# ruwido-usb.net
KiCad netlist of a schematic drawn in EAGLE
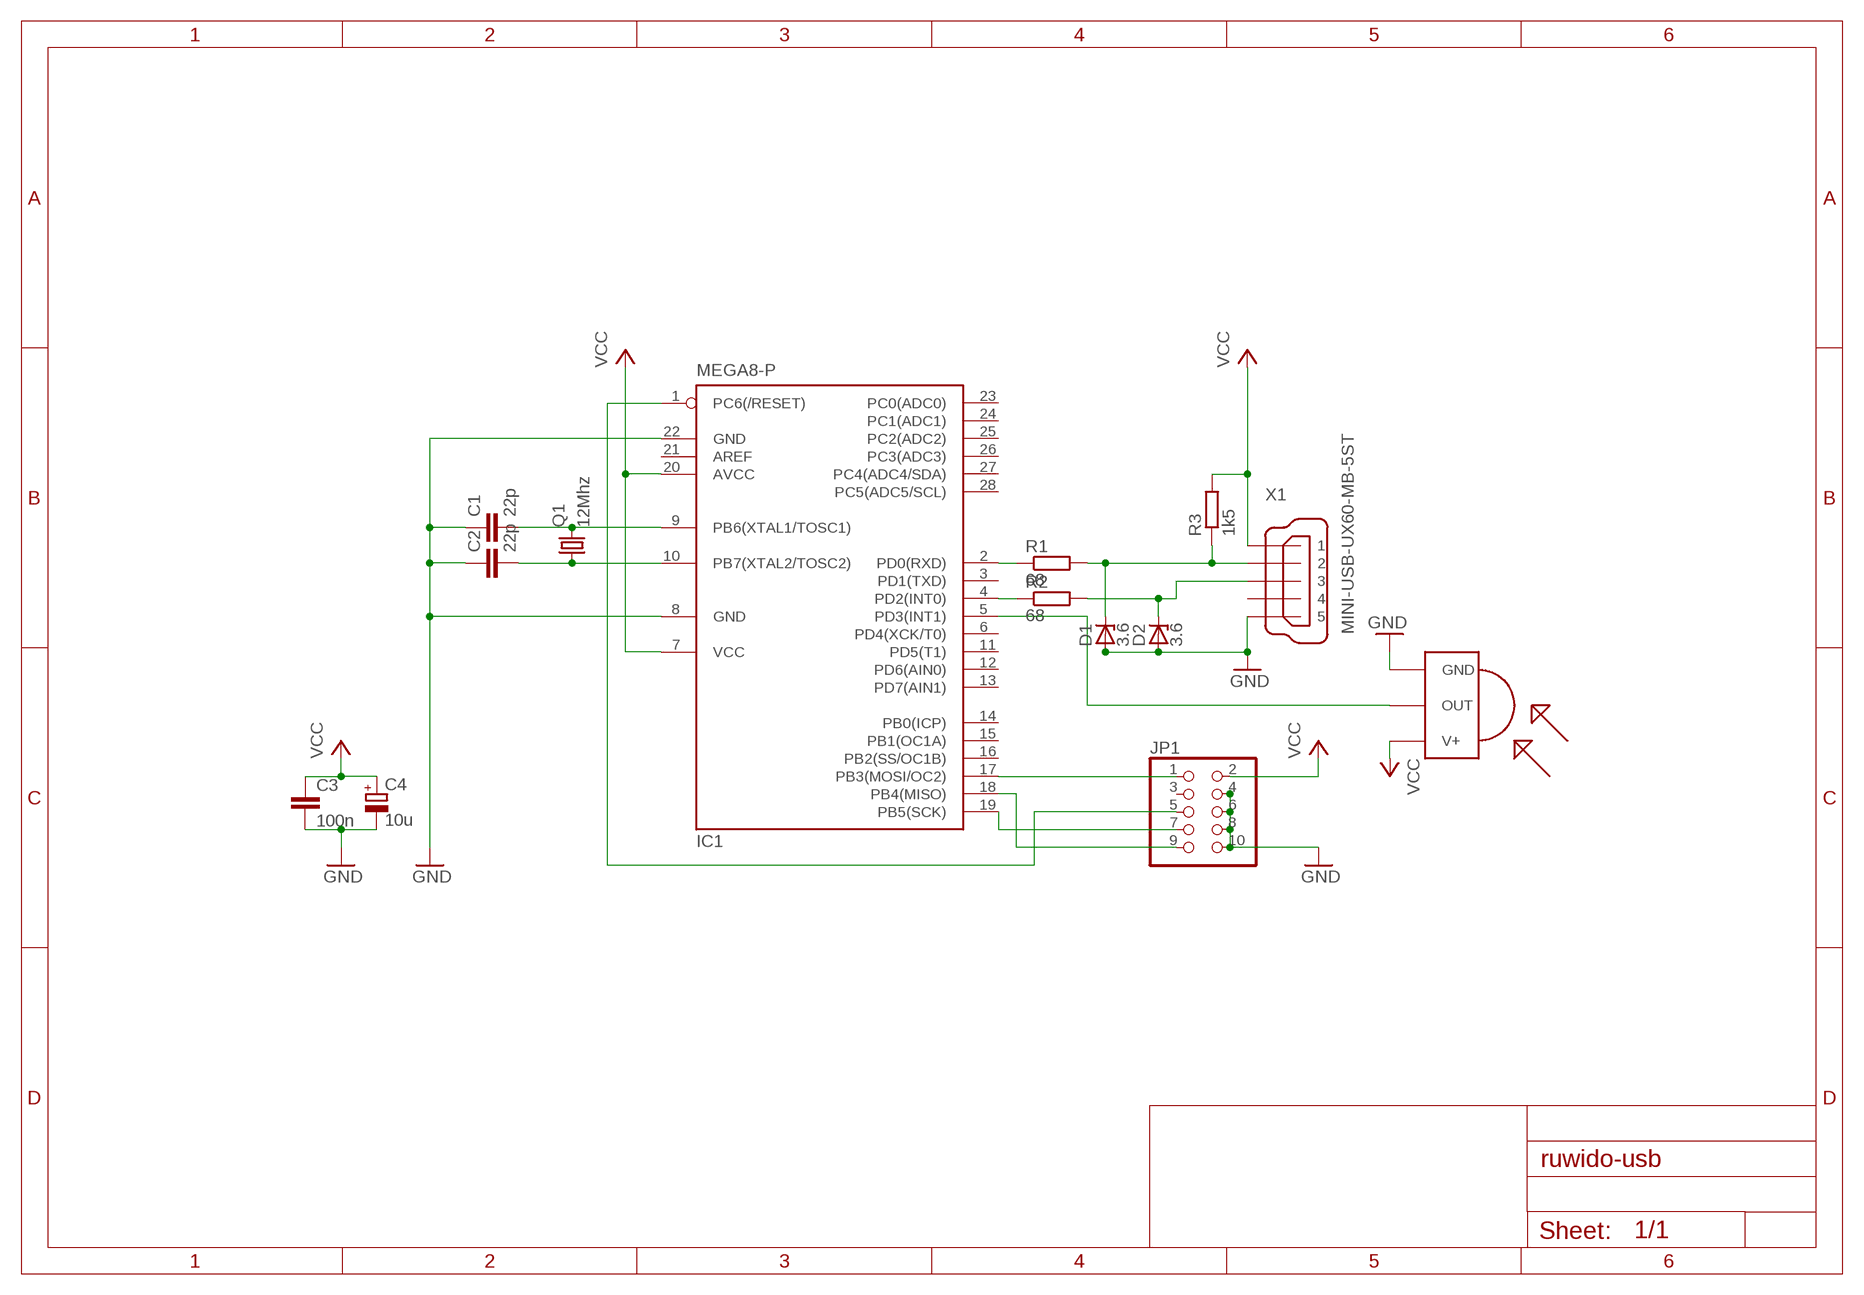
[diagram p0: schematic, sheet 1]

(export (version "E")
  (design (tool "Eeschema 10.0.6"))
  (components
    (comp (ref "C1")
      (value "22p")
      (footprint "eagle-import:C025-024X044")
      (libsource (lib "eagle-import") (part "C-EU025-024X044"))
    )
    (comp (ref "C2")
      (value "22p")
      (footprint "eagle-import:C025-024X044")
      (libsource (lib "eagle-import") (part "C-EU025-024X044"))
    )
    (comp (ref "C3")
      (value "100n")
      (footprint "eagle-import:C025-024X044")
      (libsource (lib "eagle-import") (part "C-EU025-024X044"))
    )
    (comp (ref "C4")
      (value "10u")
      (footprint "eagle-import:E2,5-6")
      (libsource (lib "eagle-import") (part "CPOL-EUE2.5-6"))
    )
    (comp (ref "D1")
      (value "3.6")
      (footprint "eagle-import:DO34Z7")
      (libsource (lib "eagle-import") (part "ZENER-DIODEDO34-7"))
    )
    (comp (ref "D2")
      (value "3.6")
      (footprint "eagle-import:DO34Z7")
      (libsource (lib "eagle-import") (part "ZENER-DIODEDO34-7"))
    )
    (comp (ref "IC1")
      (value "MEGA8-P")
      (footprint "eagle-import:DIL28-3")
      (libsource (lib "eagle-import") (part "MEGA8-P"))
    )
    (comp (ref "JP1")
      (value "PINHD-2X5")
      (footprint "eagle-import:2X05")
      (libsource (lib "eagle-import") (part "PINHD-2X5"))
    )
    (comp (ref "Q1")
      (value "12Mhz")
      (footprint "eagle-import:HC49U70")
      (libsource (lib "eagle-import") (part "CRYSTALHC49U70"))
    )
    (comp (ref "R1")
      (value "68")
      (footprint "eagle-import:0204_7")
      (libsource (lib "eagle-import") (part "R-EU_0204/7"))
    )
    (comp (ref "R2")
      (value "68")
      (footprint "eagle-import:0204_7")
      (libsource (lib "eagle-import") (part "R-EU_0204/7"))
    )
    (comp (ref "R3")
      (value "1k5")
      (footprint "eagle-import:0204_7")
      (libsource (lib "eagle-import") (part "R-EU_0204/7"))
    )
    (comp (ref "U$1")
      (value "TSOP1756")
      (footprint "eagle-import:TSOP17XX")
      (libsource (lib "eagle-import") (part "TSOP1756"))
    )
    (comp (ref "X1")
      (value "MINI-USB-UX60-MB-5ST")
      (footprint "eagle-import:UX60-MB-5ST")
      (libsource (lib "eagle-import") (part "MINI-USB-UX60-MB-5ST"))
    )
  )
  (nets
    (net (code "1") (name "GND") (class "Default")
      (node (ref "C1") (pin "1") (pinfunction "1_1") (pintype "passive"))
      (node (ref "C2") (pin "1") (pinfunction "1_1") (pintype "passive"))
      (node (ref "C3") (pin "2") (pinfunction "2_2") (pintype "passive"))
      (node (ref "C4") (pin "-") (pinfunction "-_-") (pintype "passive"))
      (node (ref "D1") (pin "A") (pinfunction "A_A") (pintype "passive"))
      (node (ref "D2") (pin "A") (pinfunction "A_A") (pintype "passive"))
      (node (ref "IC1") (pin "22") (pinfunction "GND_22") (pintype "power_in"))
      (node (ref "IC1") (pin "8") (pinfunction "GND_8") (pintype "power_in"))
      (node (ref "JP1") (pin "10") (pinfunction "10_10") (pintype "passive"))
      (node (ref "JP1") (pin "4") (pinfunction "4_4") (pintype "passive"))
      (node (ref "JP1") (pin "6") (pinfunction "6_6") (pintype "passive"))
      (node (ref "JP1") (pin "8") (pinfunction "8_8") (pintype "passive"))
      (node (ref "U$1") (pin "GND") (pinfunction "GND_GND") (pintype "bidirectional"))
      (node (ref "X1") (pin "5") (pinfunction "5_5") (pintype "input"))
    )
    (net (code "2") (name "Net-(D1-PadC)") (class "Default")
      (node (ref "D1") (pin "C") (pinfunction "C_C") (pintype "passive"))
      (node (ref "R1") (pin "2") (pinfunction "2_2") (pintype "passive"))
      (node (ref "R3") (pin "1") (pinfunction "1_1") (pintype "passive"))
      (node (ref "X1") (pin "2") (pinfunction "2_2") (pintype "input"))
    )
    (net (code "3") (name "Net-(D2-PadC)") (class "Default")
      (node (ref "D2") (pin "C") (pinfunction "C_C") (pintype "passive"))
      (node (ref "R2") (pin "2") (pinfunction "2_2") (pintype "passive"))
      (node (ref "X1") (pin "3") (pinfunction "3_3") (pintype "input"))
    )
    (net (code "4") (name "Net-(IC1-PB3(MOSI{slash}OC2))") (class "Default")
      (node (ref "IC1") (pin "17") (pinfunction "PB3(MOSI/OC2)_17") (pintype "bidirectional"))
      (node (ref "JP1") (pin "1") (pinfunction "1_1") (pintype "passive"))
    )
    (net (code "5") (name "Net-(IC1-PB4(MISO))") (class "Default")
      (node (ref "IC1") (pin "18") (pinfunction "PB4(MISO)_18") (pintype "bidirectional"))
      (node (ref "JP1") (pin "9") (pinfunction "9_9") (pintype "passive"))
    )
    (net (code "6") (name "Net-(IC1-PB5(SCK))") (class "Default")
      (node (ref "IC1") (pin "19") (pinfunction "PB5(SCK)_19") (pintype "bidirectional"))
      (node (ref "JP1") (pin "7") (pinfunction "7_7") (pintype "passive"))
    )
    (net (code "7") (name "Net-(IC1-PB6(XTAL1{slash}TOSC1))") (class "Default")
      (node (ref "C1") (pin "2") (pinfunction "2_2") (pintype "passive"))
      (node (ref "IC1") (pin "9") (pinfunction "PB6(XTAL1/TOSC1)_9") (pintype "bidirectional"))
      (node (ref "Q1") (pin "2") (pinfunction "2_2") (pintype "passive"))
    )
    (net (code "8") (name "Net-(IC1-PB7(XTAL2{slash}TOSC2))") (class "Default")
      (node (ref "C2") (pin "2") (pinfunction "2_2") (pintype "passive"))
      (node (ref "IC1") (pin "10") (pinfunction "PB7(XTAL2/TOSC2)_10") (pintype "bidirectional"))
      (node (ref "Q1") (pin "1") (pinfunction "1_1") (pintype "passive"))
    )
    (net (code "9") (name "Net-(IC1-PC6({slash}RESET))") (class "Default")
      (node (ref "IC1") (pin "1") (pinfunction "PC6(/RESET)_1") (pintype "bidirectional"))
      (node (ref "JP1") (pin "5") (pinfunction "5_5") (pintype "passive"))
    )
    (net (code "10") (name "Net-(IC1-PD0(RXD))") (class "Default")
      (node (ref "IC1") (pin "2") (pinfunction "PD0(RXD)_2") (pintype "bidirectional"))
      (node (ref "R1") (pin "1") (pinfunction "1_1") (pintype "passive"))
    )
    (net (code "11") (name "Net-(IC1-PD2(INT0))") (class "Default")
      (node (ref "IC1") (pin "4") (pinfunction "PD2(INT0)_4") (pintype "bidirectional"))
      (node (ref "R2") (pin "1") (pinfunction "1_1") (pintype "passive"))
    )
    (net (code "12") (name "Net-(IC1-PD3(INT1))") (class "Default")
      (node (ref "IC1") (pin "5") (pinfunction "PD3(INT1)_5") (pintype "bidirectional"))
      (node (ref "U$1") (pin "OUT") (pinfunction "OUT_OUT") (pintype "bidirectional"))
    )
    (net (code "13") (name "VCC") (class "Default")
      (node (ref "C3") (pin "1") (pinfunction "1_1") (pintype "passive"))
      (node (ref "C4") (pin "+") (pinfunction "+_+") (pintype "passive"))
      (node (ref "IC1") (pin "20") (pinfunction "AVCC_20") (pintype "power_in"))
      (node (ref "IC1") (pin "7") (pinfunction "VCC_7") (pintype "power_in"))
      (node (ref "JP1") (pin "2") (pinfunction "2_2") (pintype "passive"))
      (node (ref "R3") (pin "2") (pinfunction "2_2") (pintype "passive"))
      (node (ref "U$1") (pin "V+") (pinfunction "V+_V+") (pintype "bidirectional"))
      (node (ref "X1") (pin "1") (pinfunction "1_1") (pintype "input"))
    )
    (net (code "14") (name "unconnected-(IC1-AREF-Pad21)") (class "Default")
      (node (ref "IC1") (pin "21") (pinfunction "AREF_21") (pintype "passive"))
    )
    (net (code "15") (name "unconnected-(IC1-PB0(ICP)-Pad14)") (class "Default")
      (node (ref "IC1") (pin "14") (pinfunction "PB0(ICP)_14") (pintype "bidirectional"))
    )
    (net (code "16") (name "unconnected-(IC1-PB1(OC1A)-Pad15)") (class "Default")
      (node (ref "IC1") (pin "15") (pinfunction "PB1(OC1A)_15") (pintype "bidirectional"))
    )
    (net (code "17") (name "unconnected-(IC1-PB2(SS{slash}OC1B)-Pad16)") (class "Default")
      (node (ref "IC1") (pin "16") (pinfunction "PB2(SS/OC1B)_16") (pintype "bidirectional"))
    )
    (net (code "18") (name "unconnected-(IC1-PC0(ADC0)-Pad23)") (class "Default")
      (node (ref "IC1") (pin "23") (pinfunction "PC0(ADC0)_23") (pintype "bidirectional"))
    )
    (net (code "19") (name "unconnected-(IC1-PC1(ADC1)-Pad24)") (class "Default")
      (node (ref "IC1") (pin "24") (pinfunction "PC1(ADC1)_24") (pintype "bidirectional"))
    )
    (net (code "20") (name "unconnected-(IC1-PC2(ADC2)-Pad25)") (class "Default")
      (node (ref "IC1") (pin "25") (pinfunction "PC2(ADC2)_25") (pintype "bidirectional"))
    )
    (net (code "21") (name "unconnected-(IC1-PC3(ADC3)-Pad26)") (class "Default")
      (node (ref "IC1") (pin "26") (pinfunction "PC3(ADC3)_26") (pintype "bidirectional"))
    )
    (net (code "22") (name "unconnected-(IC1-PC4(ADC4{slash}SDA)-Pad27)") (class "Default")
      (node (ref "IC1") (pin "27") (pinfunction "PC4(ADC4/SDA)_27") (pintype "bidirectional"))
    )
    (net (code "23") (name "unconnected-(IC1-PC5(ADC5{slash}SCL)-Pad28)") (class "Default")
      (node (ref "IC1") (pin "28") (pinfunction "PC5(ADC5/SCL)_28") (pintype "bidirectional"))
    )
    (net (code "24") (name "unconnected-(IC1-PD1(TXD)-Pad3)") (class "Default")
      (node (ref "IC1") (pin "3") (pinfunction "PD1(TXD)_3") (pintype "bidirectional"))
    )
    (net (code "25") (name "unconnected-(IC1-PD4(XCK{slash}T0)-Pad6)") (class "Default")
      (node (ref "IC1") (pin "6") (pinfunction "PD4(XCK/T0)_6") (pintype "bidirectional"))
    )
    (net (code "26") (name "unconnected-(IC1-PD5(T1)-Pad11)") (class "Default")
      (node (ref "IC1") (pin "11") (pinfunction "PD5(T1)_11") (pintype "bidirectional"))
    )
    (net (code "27") (name "unconnected-(IC1-PD6(AIN0)-Pad12)") (class "Default")
      (node (ref "IC1") (pin "12") (pinfunction "PD6(AIN0)_12") (pintype "bidirectional"))
    )
    (net (code "28") (name "unconnected-(IC1-PD7(AIN1)-Pad13)") (class "Default")
      (node (ref "IC1") (pin "13") (pinfunction "PD7(AIN1)_13") (pintype "bidirectional"))
    )
    (net (code "29") (name "unconnected-(JP1-Pad3)") (class "Default")
      (node (ref "JP1") (pin "3") (pinfunction "3_3") (pintype "passive"))
    )
    (net (code "30") (name "unconnected-(X1-Pad4)") (class "Default")
      (node (ref "X1") (pin "4") (pinfunction "4_4") (pintype "input"))
    )
  )
)
